# SparkFun_LIS3DH-Breakout.net
KiCad netlist of a schematic drawn in EAGLE
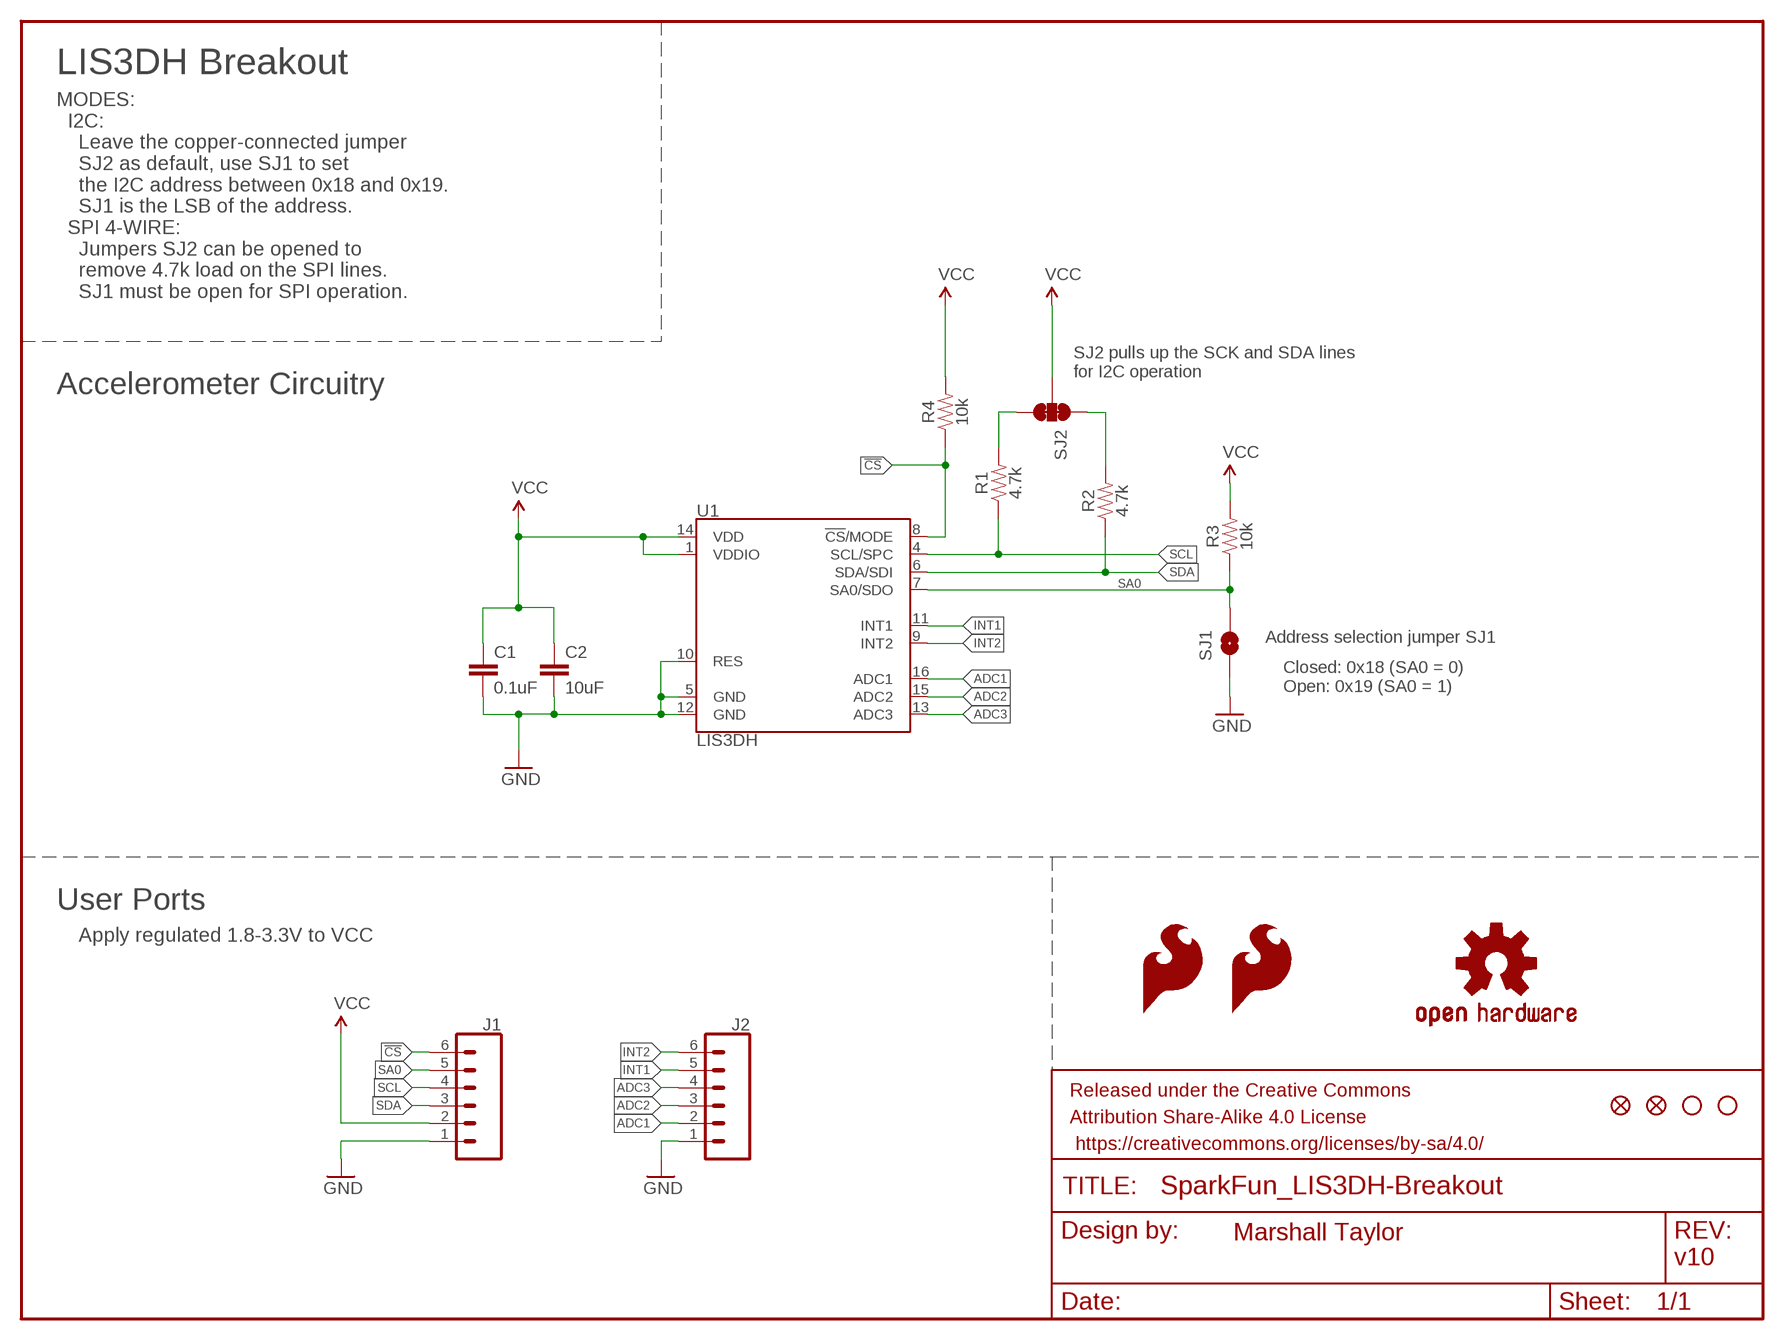
[diagram p0: schematic, sheet 1]

(export (version "E")
  (design (tool "Eeschema 10.0.6"))
  (components
    (comp (ref "C1")
      (value "0.1uF")
      (footprint "eagle-import:0402")
      (libsource (lib "eagle-import") (part "0.1UF-0402-16V-10%"))
    )
    (comp (ref "C2")
      (value "10uF")
      (footprint "eagle-import:0603")
      (libsource (lib "eagle-import") (part "10UF-0603-6.3V-20%"))
    )
    (comp (ref "FRAME2")
      (value "FRAME-LETTER")
      (footprint "eagle-import:CREATIVE_COMMONS")
      (libsource (lib "eagle-import") (part "FRAME-LETTER"))
    )
    (comp (ref "J1")
      (value "CONN_06NO_SILK_FEMALE_PTH")
      (footprint "eagle-import:1X06_NO_SILK")
      (libsource (lib "eagle-import") (part "CONN_06NO_SILK_FEMALE_PTH"))
    )
    (comp (ref "J2")
      (value "CONN_06NO_SILK_FEMALE_PTH")
      (footprint "eagle-import:1X06_NO_SILK")
      (libsource (lib "eagle-import") (part "CONN_06NO_SILK_FEMALE_PTH"))
    )
    (comp (ref "JP2")
      (value "FIDUCIALUFIDUCIAL")
      (footprint "eagle-import:MICRO-FIDUCIAL")
      (libsource (lib "eagle-import") (part "FIDUCIALUFIDUCIAL"))
    )
    (comp (ref "JP3")
      (value "STAND-OFF")
      (footprint "eagle-import:STAND-OFF")
      (libsource (lib "eagle-import") (part "STAND-OFF"))
    )
    (comp (ref "JP4")
      (value "STAND-OFF")
      (footprint "eagle-import:STAND-OFF")
      (libsource (lib "eagle-import") (part "STAND-OFF"))
    )
    (comp (ref "JP6")
      (value "FIDUCIALUFIDUCIAL")
      (footprint "eagle-import:MICRO-FIDUCIAL")
      (libsource (lib "eagle-import") (part "FIDUCIALUFIDUCIAL"))
    )
    (comp (ref "LOGO1")
      (value "SFE_LOGO_FLAME.1_INCH")
      (footprint "eagle-import:SFE_LOGO_FLAME_.1")
      (libsource (lib "eagle-import") (part "SFE_LOGO_FLAME.1_INCH"))
    )
    (comp (ref "LOGO2")
      (value "SFE_LOGO_FLAME.1_INCH")
      (footprint "eagle-import:SFE_LOGO_FLAME_.1")
      (libsource (lib "eagle-import") (part "SFE_LOGO_FLAME.1_INCH"))
    )
    (comp (ref "R1")
      (value "4.7k")
      (footprint "eagle-import:0603")
      (libsource (lib "eagle-import") (part "4.7KOHM-0603-1/10W-1%"))
    )
    (comp (ref "R2")
      (value "4.7k")
      (footprint "eagle-import:0603")
      (libsource (lib "eagle-import") (part "4.7KOHM-0603-1/10W-1%"))
    )
    (comp (ref "R3")
      (value "10k")
      (footprint "eagle-import:0603")
      (libsource (lib "eagle-import") (part "10KOHM-0603-1/10W-1%"))
    )
    (comp (ref "R4")
      (value "10k")
      (footprint "eagle-import:0603")
      (libsource (lib "eagle-import") (part "10KOHM-0603-1/10W-1%"))
    )
    (comp (ref "SJ1")
      (value "SOLDERJUMPERNO")
      (footprint "eagle-import:SJ_2S-NO")
      (libsource (lib "eagle-import") (part "SOLDERJUMPERNO"))
    )
    (comp (ref "SJ2")
      (value "JUMPER-PAD-3-NC_BY_TRACE")
      (footprint "eagle-import:PAD-JUMPER-3-3OF3_NC_BY_TRACE_YES_SILK_FULL_BOX")
      (libsource (lib "eagle-import") (part "JUMPER-PAD-3-NC_BY_TRACE"))
    )
    (comp (ref "U$1")
      (value "OSHW-LOGOS")
      (footprint "eagle-import:OSHW-LOGO-S")
      (libsource (lib "eagle-import") (part "OSHW-LOGOS"))
    )
    (comp (ref "U1")
      (value "LIS3DH")
      (footprint "eagle-import:LGA-16-3X3")
      (libsource (lib "eagle-import") (part "LIS3DH"))
    )
  )
  (nets
    (net (code "1") (name "/~{CS}") (class "Default")
      (node (ref "J1") (pin "6") (pinfunction "6_6") (pintype "passive"))
      (node (ref "R4") (pin "1") (pinfunction "1_1") (pintype "passive"))
      (node (ref "U1") (pin "8") (pinfunction "~{CS}/MODE_8") (pintype "bidirectional"))
    )
    (net (code "2") (name "ADC1") (class "Default")
      (node (ref "J2") (pin "2") (pinfunction "2_2") (pintype "passive"))
      (node (ref "U1") (pin "16") (pinfunction "ADC1_16") (pintype "bidirectional"))
    )
    (net (code "3") (name "ADC2") (class "Default")
      (node (ref "J2") (pin "3") (pinfunction "3_3") (pintype "passive"))
      (node (ref "U1") (pin "15") (pinfunction "ADC2_15") (pintype "bidirectional"))
    )
    (net (code "4") (name "ADC3") (class "Default")
      (node (ref "J2") (pin "4") (pinfunction "4_4") (pintype "passive"))
      (node (ref "U1") (pin "13") (pinfunction "ADC3_13") (pintype "bidirectional"))
    )
    (net (code "5") (name "GND") (class "Default")
      (node (ref "C1") (pin "2") (pinfunction "2_2") (pintype "passive"))
      (node (ref "C2") (pin "2") (pinfunction "2_2") (pintype "passive"))
      (node (ref "J1") (pin "1") (pinfunction "1_1") (pintype "passive"))
      (node (ref "J2") (pin "1") (pinfunction "1_1") (pintype "passive"))
      (node (ref "SJ1") (pin "1") (pinfunction "1_1") (pintype "passive"))
      (node (ref "U1") (pin "10") (pinfunction "RES_10") (pintype "bidirectional"))
      (node (ref "U1") (pin "12") (pinfunction "GND_12") (pintype "bidirectional"))
      (node (ref "U1") (pin "5") (pinfunction "GND_5") (pintype "bidirectional"))
    )
    (net (code "6") (name "INT1") (class "Default")
      (node (ref "J2") (pin "5") (pinfunction "5_5") (pintype "passive"))
      (node (ref "U1") (pin "11") (pinfunction "INT1_11") (pintype "bidirectional"))
    )
    (net (code "7") (name "INT2") (class "Default")
      (node (ref "J2") (pin "6") (pinfunction "6_6") (pintype "passive"))
      (node (ref "U1") (pin "9") (pinfunction "INT2_9") (pintype "bidirectional"))
    )
    (net (code "8") (name "Net-(R1-Pad2)") (class "Default")
      (node (ref "R1") (pin "2") (pinfunction "2_2") (pintype "passive"))
      (node (ref "SJ2") (pin "3") (pinfunction "3_3") (pintype "passive"))
    )
    (net (code "9") (name "Net-(R2-Pad2)") (class "Default")
      (node (ref "R2") (pin "2") (pinfunction "2_2") (pintype "passive"))
      (node (ref "SJ2") (pin "1") (pinfunction "1_1") (pintype "passive"))
    )
    (net (code "10") (name "SA0") (class "Default")
      (node (ref "J1") (pin "5") (pinfunction "5_5") (pintype "passive"))
      (node (ref "R3") (pin "1") (pinfunction "1_1") (pintype "passive"))
      (node (ref "SJ1") (pin "2") (pinfunction "2_2") (pintype "passive"))
      (node (ref "U1") (pin "7") (pinfunction "SA0/SDO_7") (pintype "bidirectional"))
    )
    (net (code "11") (name "SCL") (class "Default")
      (node (ref "J1") (pin "4") (pinfunction "4_4") (pintype "passive"))
      (node (ref "R1") (pin "1") (pinfunction "1_1") (pintype "passive"))
      (node (ref "U1") (pin "4") (pinfunction "SCL/SPC_4") (pintype "bidirectional"))
    )
    (net (code "12") (name "SDA") (class "Default")
      (node (ref "J1") (pin "3") (pinfunction "3_3") (pintype "passive"))
      (node (ref "R2") (pin "1") (pinfunction "1_1") (pintype "passive"))
      (node (ref "U1") (pin "6") (pinfunction "SDA/SDI_6") (pintype "bidirectional"))
    )
    (net (code "13") (name "VCC") (class "Default")
      (node (ref "C1") (pin "1") (pinfunction "1_1") (pintype "passive"))
      (node (ref "C2") (pin "1") (pinfunction "1_1") (pintype "passive"))
      (node (ref "J1") (pin "2") (pinfunction "2_2") (pintype "passive"))
      (node (ref "R3") (pin "2") (pinfunction "2_2") (pintype "passive"))
      (node (ref "R4") (pin "2") (pinfunction "2_2") (pintype "passive"))
      (node (ref "SJ2") (pin "2") (pinfunction "2_2") (pintype "passive"))
      (node (ref "U1") (pin "1") (pinfunction "VDDIO_1") (pintype "bidirectional"))
      (node (ref "U1") (pin "14") (pinfunction "VDD_14") (pintype "bidirectional"))
    )
  )
)
